# isd_tower_lighting_board-v2.net
KiCad netlist of a schematic drawn in EAGLE
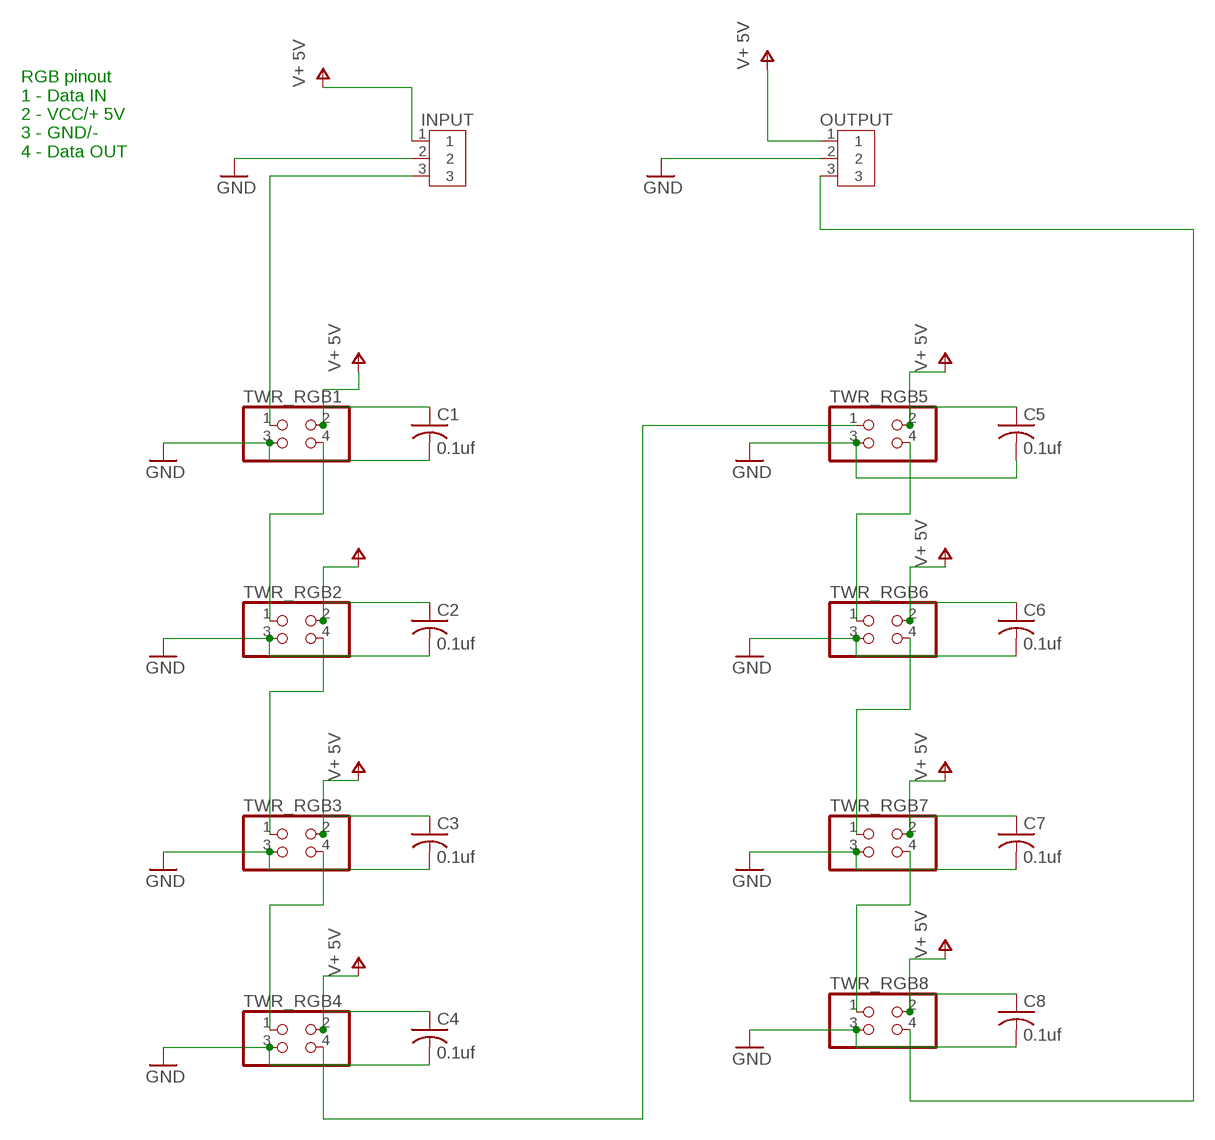
[diagram p0: schematic, sheet 1]

(export (version "E")
  (design (tool "Eeschema 10.0.6"))
  (components
    (comp (ref "C1")
      (value "0.1uf")
      (footprint "eagle-import:C0805")
      (libsource (lib "eagle-import") (part "C-USC0805"))
    )
    (comp (ref "C2")
      (value "0.1uf")
      (footprint "eagle-import:C0805")
      (libsource (lib "eagle-import") (part "C-USC0805"))
    )
    (comp (ref "C3")
      (value "0.1uf")
      (footprint "eagle-import:C0805")
      (libsource (lib "eagle-import") (part "C-USC0805"))
    )
    (comp (ref "C4")
      (value "0.1uf")
      (footprint "eagle-import:C0805")
      (libsource (lib "eagle-import") (part "C-USC0805"))
    )
    (comp (ref "C5")
      (value "0.1uf")
      (footprint "eagle-import:C0805")
      (libsource (lib "eagle-import") (part "C-USC0805"))
    )
    (comp (ref "C6")
      (value "0.1uf")
      (footprint "eagle-import:C0805")
      (libsource (lib "eagle-import") (part "C-USC0805"))
    )
    (comp (ref "C7")
      (value "0.1uf")
      (footprint "eagle-import:C0805")
      (libsource (lib "eagle-import") (part "C-USC0805"))
    )
    (comp (ref "C8")
      (value "0.1uf")
      (footprint "eagle-import:C0805")
      (libsource (lib "eagle-import") (part "C-USC0805"))
    )
    (comp (ref "INPUT")
      (value "B3B-XH-A")
      (footprint "eagle-import:B3B-XH-A")
      (fields (field (name "MANUFACTURER") "JST (XH connector)"))
      (libsource (lib "eagle-import") (part "B3B-XH-A"))
    )
    (comp (ref "OUTPUT")
      (value "B3B-XH-A")
      (footprint "eagle-import:B3B-XH-A")
      (fields (field (name "MANUFACTURER") "JST (XH connector)"))
      (libsource (lib "eagle-import") (part "B3B-XH-A"))
    )
    (comp (ref "TWR_RGB1")
      (value "PINHD-2X2")
      (footprint "eagle-import:2X02")
      (libsource (lib "eagle-import") (part "PINHD-2X2"))
    )
    (comp (ref "TWR_RGB2")
      (value "PINHD-2X2")
      (footprint "eagle-import:2X02")
      (libsource (lib "eagle-import") (part "PINHD-2X2"))
    )
    (comp (ref "TWR_RGB3")
      (value "PINHD-2X2")
      (footprint "eagle-import:2X02")
      (libsource (lib "eagle-import") (part "PINHD-2X2"))
    )
    (comp (ref "TWR_RGB4")
      (value "PINHD-2X2")
      (footprint "eagle-import:2X02")
      (libsource (lib "eagle-import") (part "PINHD-2X2"))
    )
    (comp (ref "TWR_RGB5")
      (value "PINHD-2X2")
      (footprint "eagle-import:2X02")
      (libsource (lib "eagle-import") (part "PINHD-2X2"))
    )
    (comp (ref "TWR_RGB6")
      (value "PINHD-2X2")
      (footprint "eagle-import:2X02")
      (libsource (lib "eagle-import") (part "PINHD-2X2"))
    )
    (comp (ref "TWR_RGB7")
      (value "PINHD-2X2")
      (footprint "eagle-import:2X02")
      (libsource (lib "eagle-import") (part "PINHD-2X2"))
    )
    (comp (ref "TWR_RGB8")
      (value "PINHD-2X2")
      (footprint "eagle-import:2X02")
      (libsource (lib "eagle-import") (part "PINHD-2X2"))
    )
  )
  (nets
    (net (code "1") (name "GND") (class "Default")
      (node (ref "C1") (pin "2") (pinfunction "2_2") (pintype "passive"))
      (node (ref "C2") (pin "2") (pinfunction "2_2") (pintype "passive"))
      (node (ref "C3") (pin "2") (pinfunction "2_2") (pintype "passive"))
      (node (ref "C4") (pin "2") (pinfunction "2_2") (pintype "passive"))
      (node (ref "C5") (pin "2") (pinfunction "2_2") (pintype "passive"))
      (node (ref "C6") (pin "2") (pinfunction "2_2") (pintype "passive"))
      (node (ref "C7") (pin "2") (pinfunction "2_2") (pintype "passive"))
      (node (ref "C8") (pin "2") (pinfunction "2_2") (pintype "passive"))
      (node (ref "INPUT") (pin "2") (pinfunction "2_2") (pintype "bidirectional"))
      (node (ref "OUTPUT") (pin "2") (pinfunction "2_2") (pintype "bidirectional"))
      (node (ref "TWR_RGB1") (pin "3") (pinfunction "3_3") (pintype "passive"))
      (node (ref "TWR_RGB2") (pin "3") (pinfunction "3_3") (pintype "passive"))
      (node (ref "TWR_RGB3") (pin "3") (pinfunction "3_3") (pintype "passive"))
      (node (ref "TWR_RGB4") (pin "3") (pinfunction "3_3") (pintype "passive"))
      (node (ref "TWR_RGB5") (pin "3") (pinfunction "3_3") (pintype "passive"))
      (node (ref "TWR_RGB6") (pin "3") (pinfunction "3_3") (pintype "passive"))
      (node (ref "TWR_RGB7") (pin "3") (pinfunction "3_3") (pintype "passive"))
      (node (ref "TWR_RGB8") (pin "3") (pinfunction "3_3") (pintype "passive"))
    )
    (net (code "2") (name "Net-(INPUT-Pad3)") (class "Default")
      (node (ref "INPUT") (pin "3") (pinfunction "3_3") (pintype "bidirectional"))
      (node (ref "TWR_RGB1") (pin "1") (pinfunction "1_1") (pintype "passive"))
    )
    (net (code "3") (name "Net-(OUTPUT-Pad3)") (class "Default")
      (node (ref "OUTPUT") (pin "3") (pinfunction "3_3") (pintype "bidirectional"))
      (node (ref "TWR_RGB8") (pin "4") (pinfunction "4_4") (pintype "passive"))
    )
    (net (code "4") (name "Net-(TWR_RGB1-Pad4)") (class "Default")
      (node (ref "TWR_RGB1") (pin "4") (pinfunction "4_4") (pintype "passive"))
      (node (ref "TWR_RGB2") (pin "1") (pinfunction "1_1") (pintype "passive"))
    )
    (net (code "5") (name "Net-(TWR_RGB2-Pad4)") (class "Default")
      (node (ref "TWR_RGB2") (pin "4") (pinfunction "4_4") (pintype "passive"))
      (node (ref "TWR_RGB3") (pin "1") (pinfunction "1_1") (pintype "passive"))
    )
    (net (code "6") (name "Net-(TWR_RGB3-Pad4)") (class "Default")
      (node (ref "TWR_RGB3") (pin "4") (pinfunction "4_4") (pintype "passive"))
      (node (ref "TWR_RGB4") (pin "1") (pinfunction "1_1") (pintype "passive"))
    )
    (net (code "7") (name "Net-(TWR_RGB4-Pad4)") (class "Default")
      (node (ref "TWR_RGB4") (pin "4") (pinfunction "4_4") (pintype "passive"))
      (node (ref "TWR_RGB5") (pin "1") (pinfunction "1_1") (pintype "passive"))
    )
    (net (code "8") (name "Net-(TWR_RGB5-Pad4)") (class "Default")
      (node (ref "TWR_RGB5") (pin "4") (pinfunction "4_4") (pintype "passive"))
      (node (ref "TWR_RGB6") (pin "1") (pinfunction "1_1") (pintype "passive"))
    )
    (net (code "9") (name "Net-(TWR_RGB6-Pad4)") (class "Default")
      (node (ref "TWR_RGB6") (pin "4") (pinfunction "4_4") (pintype "passive"))
      (node (ref "TWR_RGB7") (pin "1") (pinfunction "1_1") (pintype "passive"))
    )
    (net (code "10") (name "Net-(TWR_RGB7-Pad4)") (class "Default")
      (node (ref "TWR_RGB7") (pin "4") (pinfunction "4_4") (pintype "passive"))
      (node (ref "TWR_RGB8") (pin "1") (pinfunction "1_1") (pintype "passive"))
    )
    (net (code "11") (name "V+ 5V") (class "Default")
      (node (ref "C1") (pin "1") (pinfunction "1_1") (pintype "passive"))
      (node (ref "C2") (pin "1") (pinfunction "1_1") (pintype "passive"))
      (node (ref "C3") (pin "1") (pinfunction "1_1") (pintype "passive"))
      (node (ref "C4") (pin "1") (pinfunction "1_1") (pintype "passive"))
      (node (ref "C5") (pin "1") (pinfunction "1_1") (pintype "passive"))
      (node (ref "C6") (pin "1") (pinfunction "1_1") (pintype "passive"))
      (node (ref "C7") (pin "1") (pinfunction "1_1") (pintype "passive"))
      (node (ref "C8") (pin "1") (pinfunction "1_1") (pintype "passive"))
      (node (ref "INPUT") (pin "1") (pinfunction "1_1") (pintype "bidirectional"))
      (node (ref "OUTPUT") (pin "1") (pinfunction "1_1") (pintype "bidirectional"))
      (node (ref "TWR_RGB1") (pin "2") (pinfunction "2_2") (pintype "passive"))
      (node (ref "TWR_RGB2") (pin "2") (pinfunction "2_2") (pintype "passive"))
      (node (ref "TWR_RGB3") (pin "2") (pinfunction "2_2") (pintype "passive"))
      (node (ref "TWR_RGB4") (pin "2") (pinfunction "2_2") (pintype "passive"))
      (node (ref "TWR_RGB5") (pin "2") (pinfunction "2_2") (pintype "passive"))
      (node (ref "TWR_RGB6") (pin "2") (pinfunction "2_2") (pintype "passive"))
      (node (ref "TWR_RGB7") (pin "2") (pinfunction "2_2") (pintype "passive"))
      (node (ref "TWR_RGB8") (pin "2") (pinfunction "2_2") (pintype "passive"))
    )
  )
)
